# Encoder.net
KiCad netlist of a schematic drawn in EAGLE
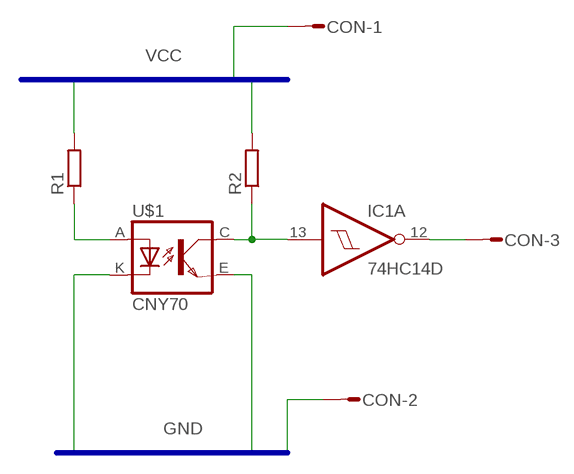
[diagram p0: schematic, sheet 1]

(export (version "E")
  (design (tool "Eeschema 10.0.6"))
  (components
    (comp (ref "CON")
      (value "L03P")
      (footprint "eagle-import:L03P")
      (libsource (lib "eagle-import") (part "L03P"))
    )
    (comp (ref "IC1")
      (value "74HC14D")
      (footprint "eagle-import:SO14")
      (libsource (lib "eagle-import") (part "7414DHC"))
    )
    (comp (ref "R1")
      (value "R-EU_M1206")
      (footprint "eagle-import:M1206")
      (libsource (lib "eagle-import") (part "R-EU_M1206"))
    )
    (comp (ref "R2")
      (value "R-EU_M1206")
      (footprint "eagle-import:M1206")
      (libsource (lib "eagle-import") (part "R-EU_M1206"))
    )
    (comp (ref "U$1")
      (value "CNY70")
      (footprint "eagle-import:4")
      (libsource (lib "eagle-import") (part "CNY70"))
    )
  )
  (nets
    (net (code "1") (name "/GND") (class "Default")
      (node (ref "CON") (pin "2") (pinfunction "S_2") (pintype "passive"))
      (node (ref "U$1") (pin "E") (pinfunction "EMI_E") (pintype "passive"))
      (node (ref "U$1") (pin "K") (pinfunction "C_K") (pintype "passive"))
    )
    (net (code "2") (name "/VCC") (class "Default")
      (node (ref "CON") (pin "1") (pinfunction "S_1") (pintype "passive"))
      (node (ref "R1") (pin "2") (pinfunction "2_2") (pintype "passive"))
      (node (ref "R2") (pin "2") (pinfunction "2_2") (pintype "passive"))
    )
    (net (code "5") (name "Net-(CONC-S)") (class "Default")
      (node (ref "CON") (pin "3") (pinfunction "S_3") (pintype "passive"))
      (node (ref "IC1") (pin "12") (pinfunction "O_12") (pintype "output"))
    )
    (net (code "6") (name "Net-(IC1A-I)") (class "Default")
      (node (ref "IC1") (pin "13") (pinfunction "I_13") (pintype "input"))
      (node (ref "R2") (pin "1") (pinfunction "1_1") (pintype "passive"))
      (node (ref "U$1") (pin "C") (pinfunction "COL_C") (pintype "passive"))
    )
    (net (code "7") (name "Net-(R1-Pad1)") (class "Default")
      (node (ref "R1") (pin "1") (pinfunction "1_1") (pintype "passive"))
      (node (ref "U$1") (pin "A") (pinfunction "A_A") (pintype "passive"))
    )
  )
)
